# Data_Logger.net
KiCad netlist of a schematic drawn in EAGLE
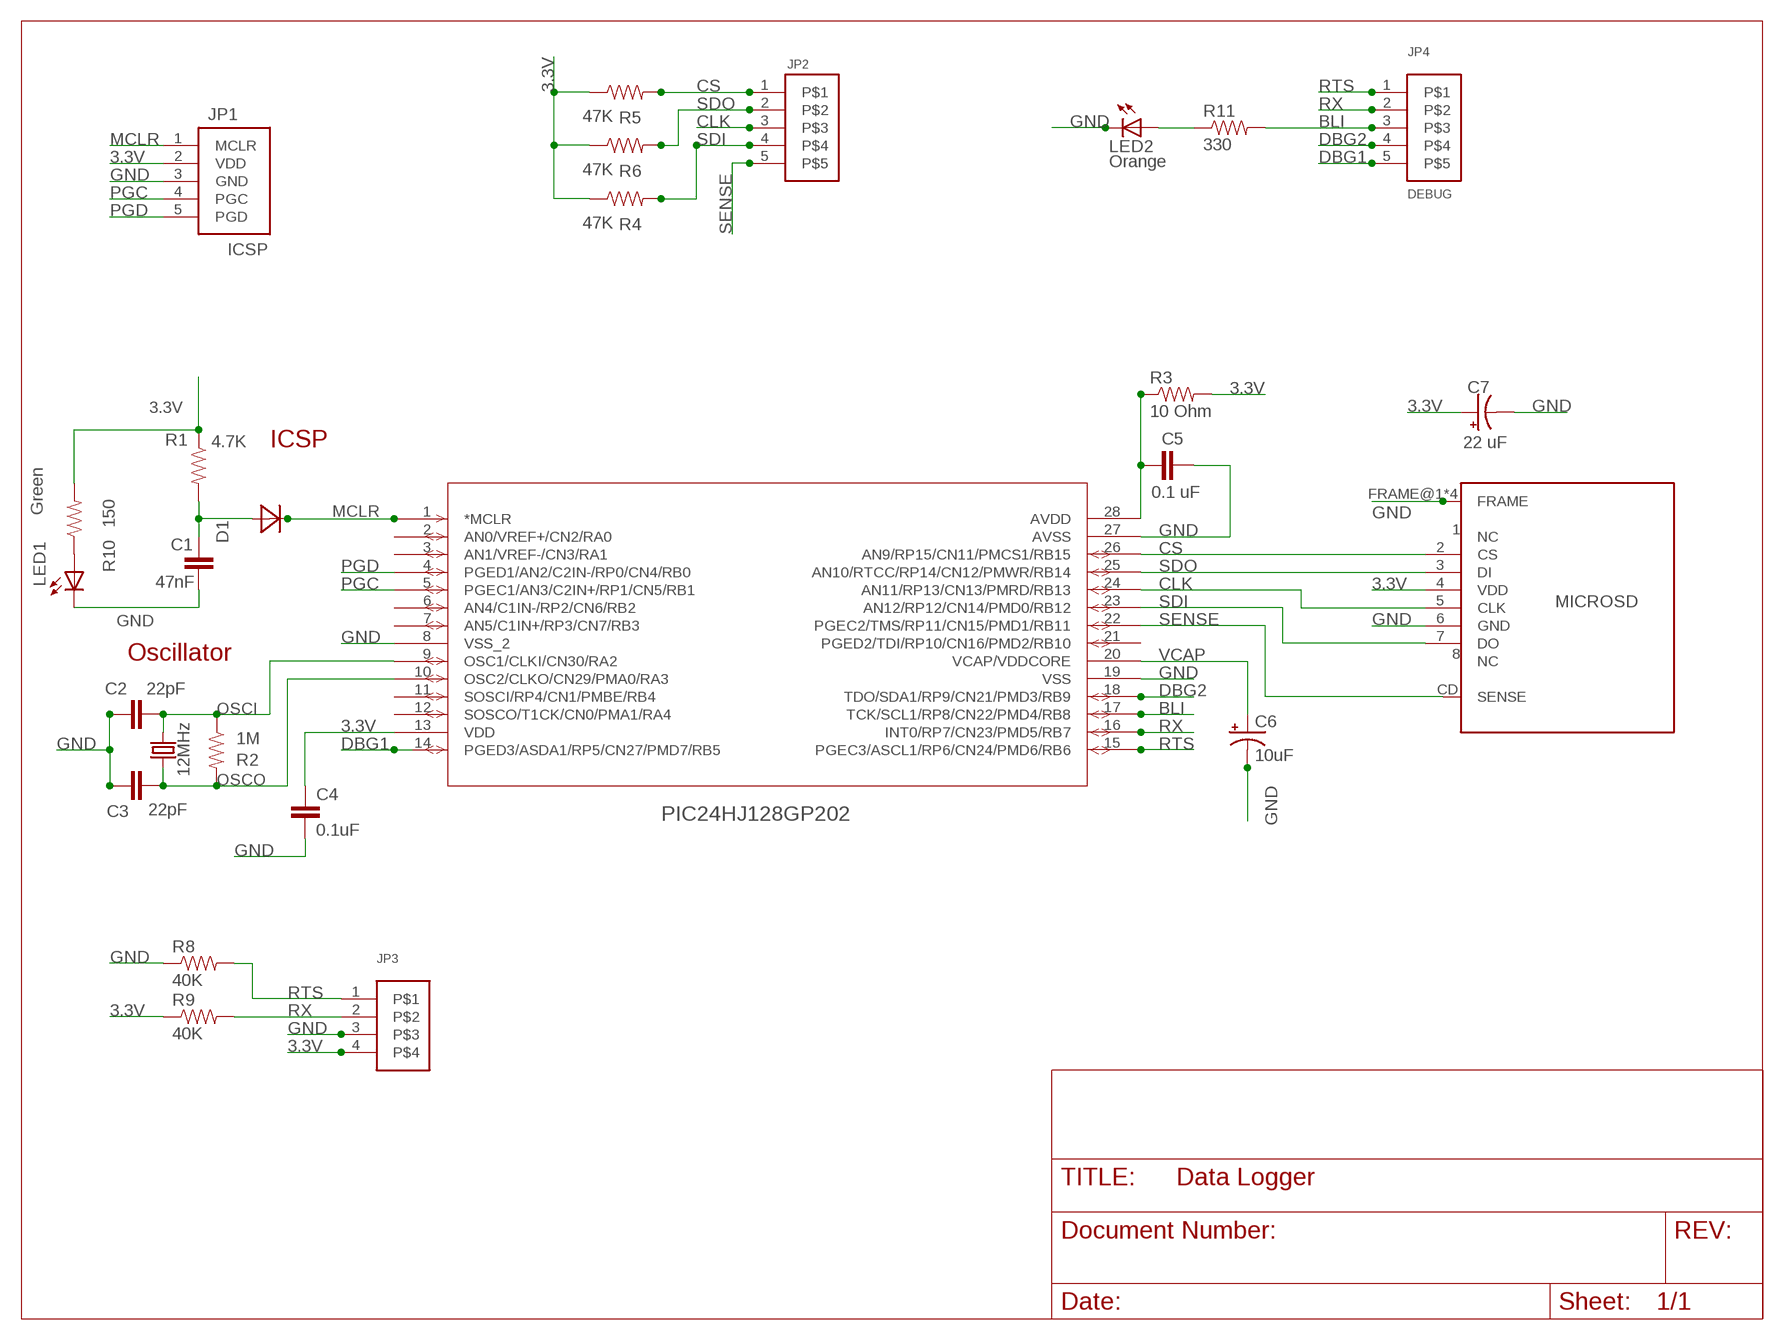
[diagram p0: schematic, sheet 1]

(export (version "E")
  (design (tool "Eeschema 10.0.6"))
  (components
    (comp (ref "C1")
      (value "47nF")
      (footprint "eagle-import:0805_INCH-HS-CAP")
      (libsource (lib "eagle-import") (part "CAP-SMD-CER0805"))
    )
    (comp (ref "C2")
      (value "22pF")
      (footprint "eagle-import:0805_INCH-HS-CAP")
      (libsource (lib "eagle-import") (part "CAP-SMD-CER0805"))
    )
    (comp (ref "C3")
      (value "22pF")
      (footprint "eagle-import:0805_INCH-HS-CAP")
      (libsource (lib "eagle-import") (part "CAP-SMD-CER0805"))
    )
    (comp (ref "C4")
      (value "0.1uF")
      (footprint "eagle-import:0805_INCH-HS-CAP")
      (libsource (lib "eagle-import") (part "CAP-SMD-CER0805"))
    )
    (comp (ref "C5")
      (value "0.1 uF")
      (footprint "eagle-import:0805_INCH-HS-CAP")
      (libsource (lib "eagle-import") (part "CAP-SMD-CER0805"))
    )
    (comp (ref "C6")
      (value "10uF")
      (footprint "eagle-import:CAP-ELE-5MM")
      (libsource (lib "eagle-import") (part "CAP-ELE_TTH_5"))
    )
    (comp (ref "C7")
      (value "22 uF")
      (footprint "eagle-import:TANT-C-6032")
      (libsource (lib "eagle-import") (part "CAP-SMD-TANT_C-6032"))
    )
    (comp (ref "D1")
      (value "DIODE_TTH")
      (footprint "eagle-import:DO34-5")
      (libsource (lib "eagle-import") (part "DIODE_TTH"))
    )
    (comp (ref "JP1")
      (value "ICSP")
      (footprint "eagle-import:1X05-PRECISE")
      (libsource (lib "eagle-import") (part "ICSP_PRECISE"))
    )
    (comp (ref "JP2")
      (value "HEADER-05_MACHINED")
      (footprint "eagle-import:1X05_MACHINED")
      (libsource (lib "eagle-import") (part "HEADER-05_MACHINED"))
    )
    (comp (ref "JP3")
      (value "HEADER-04_PRECISE-NO-SILK")
      (footprint "eagle-import:1X04-PRECISE-NO-SILK")
      (libsource (lib "eagle-import") (part "HEADER-04_PRECISE-NO-SILK"))
    )
    (comp (ref "JP4")
      (value "DEBUG")
      (footprint "eagle-import:1X05_MACHINED")
      (libsource (lib "eagle-import") (part "HEADER-05_MACHINED"))
    )
    (comp (ref "LED1")
      (value "Green")
      (footprint "eagle-import:1206_INCH-HS-LED")
      (libsource (lib "eagle-import") (part "LED_SMD_1206"))
    )
    (comp (ref "LED2")
      (value "Orange")
      (footprint "eagle-import:1206_INCH-HS-LED")
      (libsource (lib "eagle-import") (part "LED_SMD_1206"))
    )
    (comp (ref "Q1")
      (value "12MHz")
      (footprint "eagle-import:CRYSTAL-SMD-5.0X3.2")
      (libsource (lib "eagle-import") (part "CRYSTAL_SMD-5.0X3.2"))
    )
    (comp (ref "R1")
      (value "4.7K")
      (footprint "eagle-import:0805_INCH-HS")
      (libsource (lib "eagle-import") (part "RES-SMD0805"))
    )
    (comp (ref "R2")
      (value "1M")
      (footprint "eagle-import:0805_INCH-HS")
      (libsource (lib "eagle-import") (part "RES-SMD0805"))
    )
    (comp (ref "R3")
      (value "10 Ohm")
      (footprint "eagle-import:0805_INCH-HS")
      (libsource (lib "eagle-import") (part "RES-SMD0805"))
    )
    (comp (ref "R4")
      (value "47K")
      (footprint "eagle-import:0805_INCH-HS")
      (libsource (lib "eagle-import") (part "RES-SMD0805"))
    )
    (comp (ref "R5")
      (value "47K")
      (footprint "eagle-import:0805_INCH-HS")
      (libsource (lib "eagle-import") (part "RES-SMD0805"))
    )
    (comp (ref "R6")
      (value "47K")
      (footprint "eagle-import:0805_INCH-HS")
      (libsource (lib "eagle-import") (part "RESISTOR_0805"))
    )
    (comp (ref "R8")
      (value "40K")
      (footprint "eagle-import:0805_INCH-HS")
      (libsource (lib "eagle-import") (part "RESISTOR_0805"))
    )
    (comp (ref "R9")
      (value "40K")
      (footprint "eagle-import:0805_INCH-HS")
      (libsource (lib "eagle-import") (part "RESISTOR_0805"))
    )
    (comp (ref "R10")
      (value "150")
      (footprint "eagle-import:0805_INCH-HS")
      (libsource (lib "eagle-import") (part "RESISTOR_0805"))
    )
    (comp (ref "R11")
      (value "330")
      (footprint "eagle-import:0805_INCH-HS")
      (libsource (lib "eagle-import") (part "RESISTOR_0805"))
    )
    (comp (ref "U$1")
      (value "PIC24HJ128GP202")
      (footprint "eagle-import:SOIC28-W_MC")
      (libsource (lib "eagle-import") (part "PIC24HJ128GP202"))
    )
    (comp (ref "U$2")
      (value "MICROSD")
      (footprint "eagle-import:MICROSD_V1")
      (libsource (lib "eagle-import") (part "MICROSD"))
    )
  )
  (nets
    (net (code "1") (name "/3.3V") (class "Default")
      (node (ref "C4") (pin "1") (pinfunction "1_1") (pintype "passive"))
      (node (ref "C7") (pin "+") (pinfunction "+_+") (pintype "passive"))
      (node (ref "JP1") (pin "2") (pinfunction "VDD_2") (pintype "bidirectional"))
      (node (ref "JP3") (pin "4") (pinfunction "P$4_4") (pintype "bidirectional"))
      (node (ref "R1") (pin "1") (pinfunction "1_1") (pintype "passive"))
      (node (ref "R10") (pin "2") (pinfunction "2_2") (pintype "passive"))
      (node (ref "R3") (pin "2") (pinfunction "2_2") (pintype "passive"))
      (node (ref "R4") (pin "1") (pinfunction "1_1") (pintype "passive"))
      (node (ref "R5") (pin "1") (pinfunction "1_1") (pintype "passive"))
      (node (ref "R6") (pin "1") (pinfunction "1_1") (pintype "passive"))
      (node (ref "R9") (pin "1") (pinfunction "1_1") (pintype "passive"))
      (node (ref "U$1") (pin "13") (pinfunction "VDD_13") (pintype "passive"))
      (node (ref "U$2") (pin "4") (pinfunction "VDD_4") (pintype "power_in"))
    )
    (net (code "2") (name "/BLI") (class "Default")
      (node (ref "JP4") (pin "3") (pinfunction "P$3_3") (pintype "bidirectional"))
      (node (ref "R11") (pin "2") (pinfunction "2_2") (pintype "passive"))
      (node (ref "U$1") (pin "17") (pinfunction "TCK/SCL1/RP8/CN22/PMD4/RB8_17") (pintype "passive"))
    )
    (net (code "3") (name "/CLK") (class "Default")
      (node (ref "JP2") (pin "3") (pinfunction "P$3_3") (pintype "bidirectional"))
      (node (ref "U$1") (pin "24") (pinfunction "AN11/RP13/CN13/PMRD/RB13_24") (pintype "passive"))
      (node (ref "U$2") (pin "5") (pinfunction "CLK_5") (pintype "input"))
    )
    (net (code "4") (name "/CS") (class "Default")
      (node (ref "JP2") (pin "1") (pinfunction "P$1_1") (pintype "bidirectional"))
      (node (ref "R5") (pin "2") (pinfunction "2_2") (pintype "passive"))
      (node (ref "U$1") (pin "26") (pinfunction "AN9/RP15/CN11/PMCS1/RB15_26") (pintype "passive"))
      (node (ref "U$2") (pin "2") (pinfunction "CS_2") (pintype "input"))
    )
    (net (code "5") (name "/DBG1") (class "Default")
      (node (ref "JP4") (pin "5") (pinfunction "P$5_5") (pintype "bidirectional"))
      (node (ref "U$1") (pin "14") (pinfunction "PGED3/ASDA1/RP5/CN27/PMD7/RB5_14") (pintype "passive"))
    )
    (net (code "6") (name "/DBG2") (class "Default")
      (node (ref "JP4") (pin "4") (pinfunction "P$4_4") (pintype "bidirectional"))
      (node (ref "U$1") (pin "18") (pinfunction "TDO/SDA1/RP9/CN21/PMD3/RB9_18") (pintype "passive"))
    )
    (net (code "7") (name "/GND") (class "Default")
      (node (ref "C1") (pin "2") (pinfunction "2_2") (pintype "passive"))
      (node (ref "C2") (pin "1") (pinfunction "1_1") (pintype "passive"))
      (node (ref "C3") (pin "1") (pinfunction "1_1") (pintype "passive"))
      (node (ref "C4") (pin "2") (pinfunction "2_2") (pintype "passive"))
      (node (ref "C5") (pin "2") (pinfunction "2_2") (pintype "passive"))
      (node (ref "C6") (pin "-") (pinfunction "-_-") (pintype "passive"))
      (node (ref "C7") (pin "-") (pinfunction "-_-") (pintype "passive"))
      (node (ref "JP1") (pin "3") (pinfunction "GND_3") (pintype "bidirectional"))
      (node (ref "JP3") (pin "3") (pinfunction "P$3_3") (pintype "bidirectional"))
      (node (ref "LED1") (pin "C") (pinfunction "C_C") (pintype "passive"))
      (node (ref "LED2") (pin "C") (pinfunction "C_C") (pintype "passive"))
      (node (ref "R8") (pin "1") (pinfunction "1_1") (pintype "passive"))
      (node (ref "U$1") (pin "19") (pinfunction "VSS_19") (pintype "passive"))
      (node (ref "U$1") (pin "27") (pinfunction "AVSS_27") (pintype "passive"))
      (node (ref "U$1") (pin "8") (pinfunction "VSS_2_8") (pintype "passive"))
      (node (ref "U$2") (pin "6") (pinfunction "GND_6") (pintype "power_in"))
      (node (ref "U$2") (pin "FRAME@1") (pinfunction "FRAME_FRAME@1") (pintype "power_in"))
      (node (ref "U$2") (pin "FRAME@2") (pinfunction "FRAME_FRAME@2") (pintype "power_in"))
      (node (ref "U$2") (pin "FRAME@3") (pinfunction "FRAME_FRAME@3") (pintype "power_in"))
      (node (ref "U$2") (pin "FRAME@4") (pinfunction "FRAME_FRAME@4") (pintype "power_in"))
    )
    (net (code "8") (name "/MCLR") (class "Default")
      (node (ref "D1") (pin "C") (pinfunction "C_C") (pintype "passive"))
      (node (ref "JP1") (pin "1") (pinfunction "MCLR_1") (pintype "bidirectional"))
      (node (ref "U$1") (pin "1") (pinfunction "*MCLR_1") (pintype "passive"))
    )
    (net (code "9") (name "/OSCI") (class "Default")
      (node (ref "C2") (pin "2") (pinfunction "2_2") (pintype "passive"))
      (node (ref "Q1") (pin "P$2") (pinfunction "2_P$2") (pintype "passive"))
      (node (ref "R2") (pin "1") (pinfunction "1_1") (pintype "passive"))
      (node (ref "U$1") (pin "9") (pinfunction "OSC1/CLKI/CN30/RA2_9") (pintype "passive"))
    )
    (net (code "10") (name "/OSCO") (class "Default")
      (node (ref "C3") (pin "2") (pinfunction "2_2") (pintype "passive"))
      (node (ref "Q1") (pin "P$1") (pinfunction "1_P$1") (pintype "passive"))
      (node (ref "R2") (pin "2") (pinfunction "2_2") (pintype "passive"))
      (node (ref "U$1") (pin "10") (pinfunction "OSC2/CLKO/CN29/PMA0/RA3_10") (pintype "passive"))
    )
    (net (code "11") (name "/PGC") (class "Default")
      (node (ref "JP1") (pin "4") (pinfunction "PGC_4") (pintype "bidirectional"))
      (node (ref "U$1") (pin "5") (pinfunction "PGEC1/AN3/C2IN+/RP1/CN5/RB1_5") (pintype "passive"))
    )
    (net (code "12") (name "/PGD") (class "Default")
      (node (ref "JP1") (pin "5") (pinfunction "PGD_5") (pintype "bidirectional"))
      (node (ref "U$1") (pin "4") (pinfunction "PGED1/AN2/C2IN-/RP0/CN4/RB0_4") (pintype "passive"))
    )
    (net (code "13") (name "/RTS") (class "Default")
      (node (ref "JP3") (pin "1") (pinfunction "P$1_1") (pintype "bidirectional"))
      (node (ref "JP4") (pin "1") (pinfunction "P$1_1") (pintype "bidirectional"))
      (node (ref "R8") (pin "2") (pinfunction "2_2") (pintype "passive"))
      (node (ref "U$1") (pin "15") (pinfunction "PGEC3/ASCL1/RP6/CN24/PMD6/RB6_15") (pintype "passive"))
    )
    (net (code "14") (name "/RX") (class "Default")
      (node (ref "JP3") (pin "2") (pinfunction "P$2_2") (pintype "bidirectional"))
      (node (ref "JP4") (pin "2") (pinfunction "P$2_2") (pintype "bidirectional"))
      (node (ref "R9") (pin "2") (pinfunction "2_2") (pintype "passive"))
      (node (ref "U$1") (pin "16") (pinfunction "INT0/RP7/CN23/PMD5/RB7_16") (pintype "passive"))
    )
    (net (code "15") (name "/SDI") (class "Default")
      (node (ref "JP2") (pin "4") (pinfunction "P$4_4") (pintype "bidirectional"))
      (node (ref "R4") (pin "2") (pinfunction "2_2") (pintype "passive"))
      (node (ref "U$1") (pin "23") (pinfunction "AN12/RP12/CN14/PMD0/RB12_23") (pintype "passive"))
      (node (ref "U$2") (pin "7") (pinfunction "DO_7") (pintype "output"))
    )
    (net (code "16") (name "/SDO") (class "Default")
      (node (ref "JP2") (pin "2") (pinfunction "P$2_2") (pintype "bidirectional"))
      (node (ref "R6") (pin "2") (pinfunction "2_2") (pintype "passive"))
      (node (ref "U$1") (pin "25") (pinfunction "AN10/RTCC/RP14/CN12/PMWR/RB14_25") (pintype "passive"))
      (node (ref "U$2") (pin "3") (pinfunction "DI_3") (pintype "input"))
    )
    (net (code "17") (name "/SENSE") (class "Default")
      (node (ref "JP2") (pin "5") (pinfunction "P$5_5") (pintype "bidirectional"))
      (node (ref "U$1") (pin "22") (pinfunction "PGEC2/TMS/RP11/CN15/PMD1/RB11_22") (pintype "passive"))
      (node (ref "U$2") (pin "CD") (pinfunction "SENSE_CD") (pintype "output"))
    )
    (net (code "18") (name "/VCAP") (class "Default")
      (node (ref "C6") (pin "+") (pinfunction "+_+") (pintype "passive"))
      (node (ref "U$1") (pin "20") (pinfunction "VCAP/VDDCORE_20") (pintype "passive"))
    )
    (net (code "19") (name "Net-(C1-Pad1)") (class "Default")
      (node (ref "C1") (pin "1") (pinfunction "1_1") (pintype "passive"))
      (node (ref "D1") (pin "A") (pinfunction "A_A") (pintype "passive"))
      (node (ref "R1") (pin "2") (pinfunction "2_2") (pintype "passive"))
    )
    (net (code "20") (name "Net-(LED1-PadA)") (class "Default")
      (node (ref "LED1") (pin "A") (pinfunction "A_A") (pintype "passive"))
      (node (ref "R10") (pin "1") (pinfunction "1_1") (pintype "passive"))
    )
    (net (code "21") (name "Net-(LED2-PadA)") (class "Default")
      (node (ref "LED2") (pin "A") (pinfunction "A_A") (pintype "passive"))
      (node (ref "R11") (pin "1") (pinfunction "1_1") (pintype "passive"))
    )
    (net (code "22") (name "Net-(U$1-AVDD)") (class "Default")
      (node (ref "C5") (pin "1") (pinfunction "1_1") (pintype "passive"))
      (node (ref "R3") (pin "1") (pinfunction "1_1") (pintype "passive"))
      (node (ref "U$1") (pin "28") (pinfunction "AVDD_28") (pintype "passive"))
    )
    (net (code "23") (name "unconnected-(U$1-AN0{slash}VREF+{slash}CN2{slash}RA0-Pad2)") (class "Default")
      (node (ref "U$1") (pin "2") (pinfunction "AN0/VREF+/CN2/RA0_2") (pintype "passive"))
    )
    (net (code "24") (name "unconnected-(U$1-AN1{slash}VREF-{slash}CN3{slash}RA1-Pad3)") (class "Default")
      (node (ref "U$1") (pin "3") (pinfunction "AN1/VREF-/CN3/RA1_3") (pintype "passive"))
    )
    (net (code "25") (name "unconnected-(U$1-AN4{slash}C1IN-{slash}RP2{slash}CN6{slash}RB2-Pad6)") (class "Default")
      (node (ref "U$1") (pin "6") (pinfunction "AN4/C1IN-/RP2/CN6/RB2_6") (pintype "passive"))
    )
    (net (code "26") (name "unconnected-(U$1-AN5{slash}C1IN+{slash}RP3{slash}CN7{slash}RB3-Pad7)") (class "Default")
      (node (ref "U$1") (pin "7") (pinfunction "AN5/C1IN+/RP3/CN7/RB3_7") (pintype "passive"))
    )
    (net (code "27") (name "unconnected-(U$1-PGED2{slash}TDI{slash}RP10{slash}CN16{slash}PMD2{slash}RB10-Pad21)") (class "Default")
      (node (ref "U$1") (pin "21") (pinfunction "PGED2/TDI/RP10/CN16/PMD2/RB10_21") (pintype "passive"))
    )
    (net (code "28") (name "unconnected-(U$1-SOSCI{slash}RP4{slash}CN1{slash}PMBE{slash}RB4-Pad11)") (class "Default")
      (node (ref "U$1") (pin "11") (pinfunction "SOSCI/RP4/CN1/PMBE/RB4_11") (pintype "passive"))
    )
    (net (code "29") (name "unconnected-(U$1-SOSCO{slash}T1CK{slash}CN0{slash}PMA1{slash}RA4-Pad12)") (class "Default")
      (node (ref "U$1") (pin "12") (pinfunction "SOSCO/T1CK/CN0/PMA1/RA4_12") (pintype "passive"))
    )
    (net (code "30") (name "unconnected-(U$2-NC-Pad1)") (class "Default")
      (node (ref "U$2") (pin "1") (pinfunction "NC_1") (pintype "no_connect"))
    )
    (net (code "31") (name "unconnected-(U$2-NC-Pad8)") (class "Default")
      (node (ref "U$2") (pin "8") (pinfunction "NC_8") (pintype "no_connect"))
    )
  )
)
